# TI_MotorController.net
KiCad netlist of a schematic drawn in EAGLE
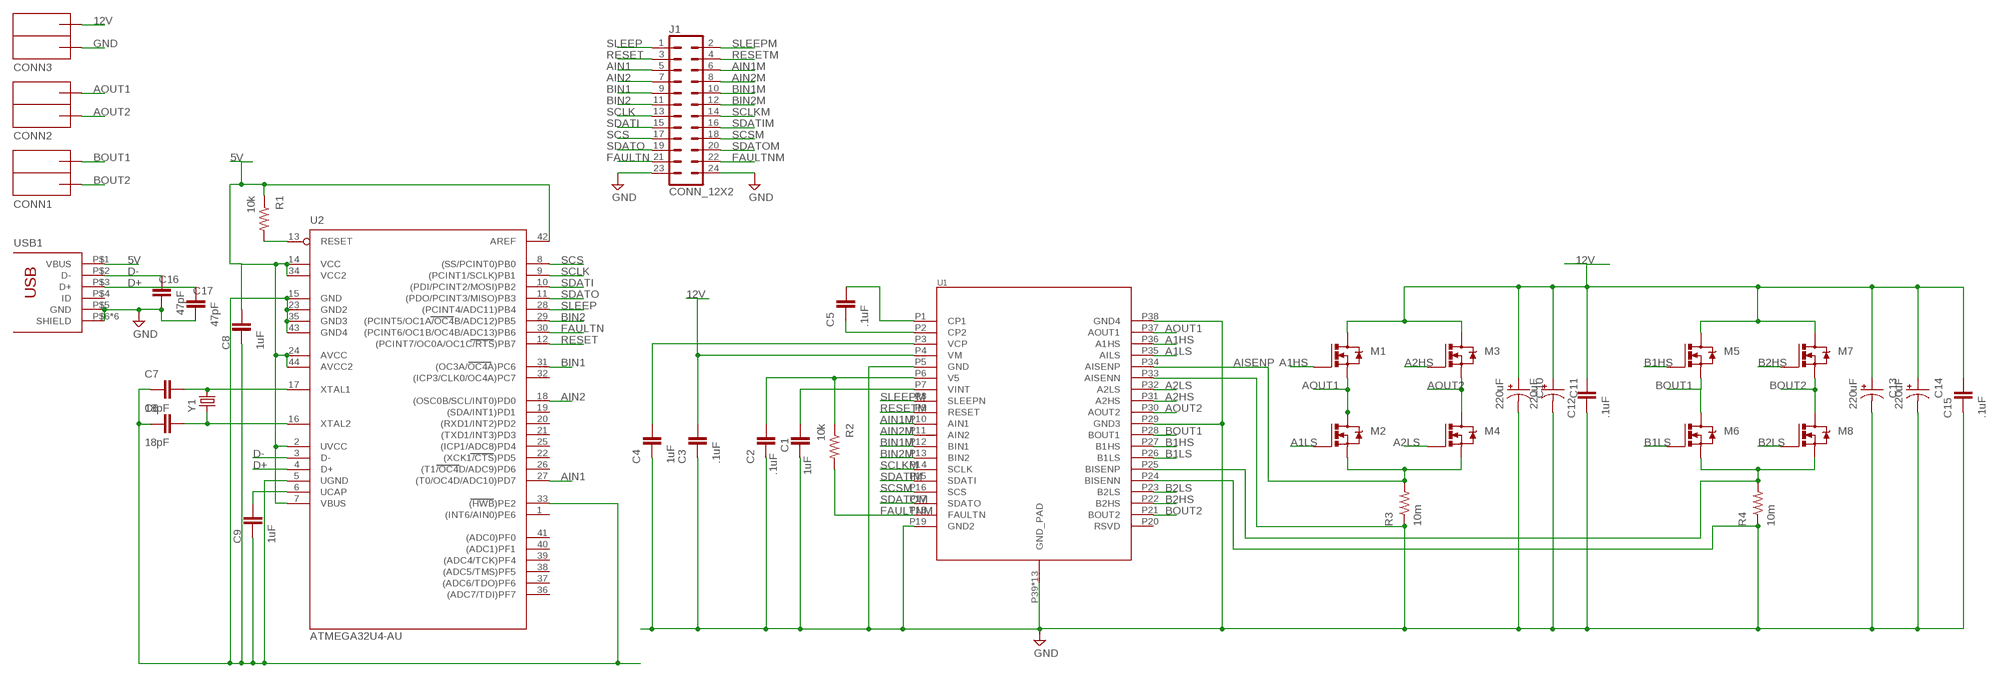
[diagram p0: schematic, sheet 1]

(export (version "E")
  (design (tool "Eeschema 10.0.6"))
  (components
    (comp (ref "C1")
      (value "1uF")
      (footprint "eagle-import:0603-CAP")
      (libsource (lib "eagle-import") (part "CAP0603-CAP"))
    )
    (comp (ref "C2")
      (value ".1uF")
      (footprint "eagle-import:0603-CAP")
      (libsource (lib "eagle-import") (part "CAP0603-CAP"))
    )
    (comp (ref "C3")
      (value ".1uF")
      (footprint "eagle-import:0603-CAP")
      (libsource (lib "eagle-import") (part "CAP0603-CAP"))
    )
    (comp (ref "C4")
      (value "1uF")
      (footprint "eagle-import:0603-CAP")
      (libsource (lib "eagle-import") (part "CAP0603-CAP"))
    )
    (comp (ref "C5")
      (value ".1uF")
      (footprint "eagle-import:0603-CAP")
      (libsource (lib "eagle-import") (part "CAP0603-CAP"))
    )
    (comp (ref "C6")
      (value "18pF")
      (footprint "eagle-import:0603-CAP")
      (libsource (lib "eagle-import") (part "CAP0603-CAP"))
    )
    (comp (ref "C7")
      (value "18pF")
      (footprint "eagle-import:0603-CAP")
      (libsource (lib "eagle-import") (part "CAP0603-CAP"))
    )
    (comp (ref "C8")
      (value "1uF")
      (footprint "eagle-import:0603-CAP")
      (libsource (lib "eagle-import") (part "CAP0603-CAP"))
    )
    (comp (ref "C9")
      (value "1uF")
      (footprint "eagle-import:0603-CAP")
      (libsource (lib "eagle-import") (part "CAP0603-CAP"))
    )
    (comp (ref "C10")
      (value "220uF")
      (footprint "eagle-import:NIPPON_F80")
      (libsource (lib "eagle-import") (part "CAP_POLF80"))
    )
    (comp (ref "C11")
      (value "220uF")
      (footprint "eagle-import:NIPPON_F80")
      (libsource (lib "eagle-import") (part "CAP_POLF80"))
    )
    (comp (ref "C12")
      (value ".1uF")
      (footprint "eagle-import:0603-CAP")
      (libsource (lib "eagle-import") (part "CAP0603-CAP"))
    )
    (comp (ref "C13")
      (value "220uF")
      (footprint "eagle-import:NIPPON_F80")
      (libsource (lib "eagle-import") (part "CAP_POLF80"))
    )
    (comp (ref "C14")
      (value "220uF")
      (footprint "eagle-import:NIPPON_F80")
      (libsource (lib "eagle-import") (part "CAP_POLF80"))
    )
    (comp (ref "C15")
      (value ".1uF")
      (footprint "eagle-import:0603-CAP")
      (libsource (lib "eagle-import") (part "CAP0603-CAP"))
    )
    (comp (ref "C16")
      (value "47pF")
      (footprint "eagle-import:0603-CAP")
      (libsource (lib "eagle-import") (part "CAP0603-CAP"))
    )
    (comp (ref "C17")
      (value "47pF")
      (footprint "eagle-import:0603-CAP")
      (libsource (lib "eagle-import") (part "CAP0603-CAP"))
    )
    (comp (ref "CONN1")
      (value "ANDERSONVERTICAL")
      (footprint "eagle-import:ANDERSON_VERTICAL")
      (libsource (lib "eagle-import") (part "ANDERSONVERTICAL"))
    )
    (comp (ref "CONN2")
      (value "ANDERSONVERTICAL")
      (footprint "eagle-import:ANDERSON_VERTICAL")
      (libsource (lib "eagle-import") (part "ANDERSONVERTICAL"))
    )
    (comp (ref "CONN3")
      (value "ANDERSONVERTICAL")
      (footprint "eagle-import:ANDERSON_VERTICAL")
      (libsource (lib "eagle-import") (part "ANDERSONVERTICAL"))
    )
    (comp (ref "J1")
      (value "CONN_12X2")
      (footprint "eagle-import:2X12")
      (libsource (lib "eagle-import") (part "CONN_12X2"))
    )
    (comp (ref "M1")
      (value "NMOS_CSD17579Q3A")
      (footprint "eagle-import:DNH0008A")
      (fields (field (name "PART_NO") "CSD17579Q3A"))
      (libsource (lib "eagle-import") (part "NMOS_CSD17579Q3A"))
    )
    (comp (ref "M2")
      (value "NMOS_CSD17579Q3A")
      (footprint "eagle-import:DNH0008A")
      (fields (field (name "PART_NO") "CSD17579Q3A"))
      (libsource (lib "eagle-import") (part "NMOS_CSD17579Q3A"))
    )
    (comp (ref "M3")
      (value "NMOS_CSD17579Q3A")
      (footprint "eagle-import:DNH0008A")
      (fields (field (name "PART_NO") "CSD17579Q3A"))
      (libsource (lib "eagle-import") (part "NMOS_CSD17579Q3A"))
    )
    (comp (ref "M4")
      (value "NMOS_CSD17579Q3A")
      (footprint "eagle-import:DNH0008A")
      (fields (field (name "PART_NO") "CSD17579Q3A"))
      (libsource (lib "eagle-import") (part "NMOS_CSD17579Q3A"))
    )
    (comp (ref "M5")
      (value "NMOS_CSD17579Q3A")
      (footprint "eagle-import:DNH0008A")
      (fields (field (name "PART_NO") "CSD17579Q3A"))
      (libsource (lib "eagle-import") (part "NMOS_CSD17579Q3A"))
    )
    (comp (ref "M6")
      (value "NMOS_CSD17579Q3A")
      (footprint "eagle-import:DNH0008A")
      (fields (field (name "PART_NO") "CSD17579Q3A"))
      (libsource (lib "eagle-import") (part "NMOS_CSD17579Q3A"))
    )
    (comp (ref "M7")
      (value "NMOS_CSD17579Q3A")
      (footprint "eagle-import:DNH0008A")
      (fields (field (name "PART_NO") "CSD17579Q3A"))
      (libsource (lib "eagle-import") (part "NMOS_CSD17579Q3A"))
    )
    (comp (ref "M8")
      (value "NMOS_CSD17579Q3A")
      (footprint "eagle-import:DNH0008A")
      (fields (field (name "PART_NO") "CSD17579Q3A"))
      (libsource (lib "eagle-import") (part "NMOS_CSD17579Q3A"))
    )
    (comp (ref "R1")
      (value "10k")
      (footprint "eagle-import:R0603")
      (fields (field (name "MANUFACTURER") "Rohm Semiconductor"))
      (libsource (lib "eagle-import") (part "R-US_R0603"))
    )
    (comp (ref "R2")
      (value "10k")
      (footprint "eagle-import:R0603")
      (fields (field (name "MANUFACTURER") "Rohm Semiconductor"))
      (libsource (lib "eagle-import") (part "R-US_R0603"))
    )
    (comp (ref "R3")
      (value "10m")
      (footprint "eagle-import:R2512")
      (libsource (lib "eagle-import") (part "R-US_R2512"))
    )
    (comp (ref "R4")
      (value "10m")
      (footprint "eagle-import:R2512")
      (libsource (lib "eagle-import") (part "R-US_R2512"))
    )
    (comp (ref "U1")
      (value "DRV8704")
      (footprint "eagle-import:HTSSOP(38)")
      (libsource (lib "eagle-import") (part "DRV8704"))
    )
    (comp (ref "U2")
      (value "ATMEGA32U4-AU")
      (footprint "eagle-import:TQFP44")
      (libsource (lib "eagle-import") (part "ATMEGA32U4-AU"))
    )
    (comp (ref "USB1")
      (value "USB-OTGMICRO-AB")
      (footprint "eagle-import:USB-MICRO-AB")
      (libsource (lib "eagle-import") (part "USB-OTGMICRO-AB"))
    )
    (comp (ref "Y1")
      (value "CRYSTAL10.5X4.8")
      (footprint "eagle-import:CRYSTAL-SMD-10.5X4.8-2PIN")
      (libsource (lib "eagle-import") (part "CRYSTAL10.5X4.8"))
    )
  )
  (nets
    (net (code "1") (name "/5V") (class "Default")
      (node (ref "C8") (pin "2") (pinfunction "2_2") (pintype "passive"))
      (node (ref "R1") (pin "1") (pinfunction "1_1") (pintype "passive"))
      (node (ref "U2") (pin "14") (pinfunction "VCC_14") (pintype "bidirectional"))
      (node (ref "U2") (pin "2") (pinfunction "UVCC_2") (pintype "bidirectional"))
      (node (ref "U2") (pin "24") (pinfunction "AVCC_24") (pintype "bidirectional"))
      (node (ref "U2") (pin "34") (pinfunction "VCC2_34") (pintype "bidirectional"))
      (node (ref "U2") (pin "42") (pinfunction "AREF_42") (pintype "bidirectional"))
      (node (ref "U2") (pin "44") (pinfunction "AVCC2_44") (pintype "bidirectional"))
      (node (ref "U2") (pin "7") (pinfunction "VBUS_7") (pintype "bidirectional"))
      (node (ref "USB1") (pin "P$1") (pinfunction "VBUS_P$1") (pintype "bidirectional"))
    )
    (net (code "2") (name "/12V") (class "Default")
      (node (ref "C10") (pin "+") (pinfunction "+_+") (pintype "passive"))
      (node (ref "C11") (pin "+") (pinfunction "+_+") (pintype "passive"))
      (node (ref "C12") (pin "2") (pinfunction "2_2") (pintype "passive"))
      (node (ref "C13") (pin "+") (pinfunction "+_+") (pintype "passive"))
      (node (ref "C14") (pin "+") (pinfunction "+_+") (pintype "passive"))
      (node (ref "C15") (pin "2") (pinfunction "2_2") (pintype "passive"))
      (node (ref "C3") (pin "2") (pinfunction "2_2") (pintype "passive"))
      (node (ref "CONN3") (pin "PIN1") (pinfunction "OUTB_PIN1") (pintype "bidirectional"))
      (node (ref "M1") (pin "5") (pinfunction "D_5") (pintype "passive"))
      (node (ref "M1") (pin "6") (pinfunction "D_6") (pintype "passive"))
      (node (ref "M1") (pin "7") (pinfunction "D_7") (pintype "passive"))
      (node (ref "M1") (pin "8") (pinfunction "D_8") (pintype "passive"))
      (node (ref "M1") (pin "9") (pinfunction "D_9") (pintype "passive"))
      (node (ref "M3") (pin "5") (pinfunction "D_5") (pintype "passive"))
      (node (ref "M3") (pin "6") (pinfunction "D_6") (pintype "passive"))
      (node (ref "M3") (pin "7") (pinfunction "D_7") (pintype "passive"))
      (node (ref "M3") (pin "8") (pinfunction "D_8") (pintype "passive"))
      (node (ref "M3") (pin "9") (pinfunction "D_9") (pintype "passive"))
      (node (ref "M5") (pin "5") (pinfunction "D_5") (pintype "passive"))
      (node (ref "M5") (pin "6") (pinfunction "D_6") (pintype "passive"))
      (node (ref "M5") (pin "7") (pinfunction "D_7") (pintype "passive"))
      (node (ref "M5") (pin "8") (pinfunction "D_8") (pintype "passive"))
      (node (ref "M5") (pin "9") (pinfunction "D_9") (pintype "passive"))
      (node (ref "M7") (pin "5") (pinfunction "D_5") (pintype "passive"))
      (node (ref "M7") (pin "6") (pinfunction "D_6") (pintype "passive"))
      (node (ref "M7") (pin "7") (pinfunction "D_7") (pintype "passive"))
      (node (ref "M7") (pin "8") (pinfunction "D_8") (pintype "passive"))
      (node (ref "M7") (pin "9") (pinfunction "D_9") (pintype "passive"))
      (node (ref "U1") (pin "P4") (pinfunction "VM_P4") (pintype "bidirectional"))
    )
    (net (code "3") (name "/A1HS") (class "Default")
      (node (ref "M1") (pin "4") (pinfunction "G_4") (pintype "passive"))
      (node (ref "U1") (pin "P36") (pinfunction "A1HS_P36") (pintype "bidirectional"))
    )
    (net (code "4") (name "/A1LS") (class "Default")
      (node (ref "M2") (pin "4") (pinfunction "G_4") (pintype "passive"))
      (node (ref "U1") (pin "P35") (pinfunction "AILS_P35") (pintype "bidirectional"))
    )
    (net (code "5") (name "/A2HS") (class "Default")
      (node (ref "M3") (pin "4") (pinfunction "G_4") (pintype "passive"))
      (node (ref "U1") (pin "P31") (pinfunction "A2HS_P31") (pintype "bidirectional"))
    )
    (net (code "6") (name "/A2LS") (class "Default")
      (node (ref "M4") (pin "4") (pinfunction "G_4") (pintype "passive"))
      (node (ref "U1") (pin "P32") (pinfunction "A2LS_P32") (pintype "bidirectional"))
    )
    (net (code "7") (name "/AIN1") (class "Default")
      (node (ref "J1") (pin "5") (pinfunction "5_5") (pintype "passive"))
      (node (ref "U2") (pin "27") (pinfunction "(T0/OC4D/ADC10)PD7_27") (pintype "bidirectional"))
    )
    (net (code "8") (name "/AIN1M") (class "Default")
      (node (ref "J1") (pin "6") (pinfunction "6_6") (pintype "passive"))
      (node (ref "U1") (pin "P10") (pinfunction "AIN1_P10") (pintype "bidirectional"))
    )
    (net (code "9") (name "/AIN2") (class "Default")
      (node (ref "J1") (pin "7") (pinfunction "7_7") (pintype "passive"))
      (node (ref "U2") (pin "18") (pinfunction "(OSC0B/SCL/INT0)PD0_18") (pintype "bidirectional"))
    )
    (net (code "10") (name "/AIN2M") (class "Default")
      (node (ref "J1") (pin "8") (pinfunction "8_8") (pintype "passive"))
      (node (ref "U1") (pin "P11") (pinfunction "AIN2_P11") (pintype "bidirectional"))
    )
    (net (code "11") (name "/AISENP") (class "Default")
      (node (ref "M2") (pin "1") (pinfunction "S_1") (pintype "passive"))
      (node (ref "M2") (pin "2") (pinfunction "S_2") (pintype "passive"))
      (node (ref "M2") (pin "3") (pinfunction "S_3") (pintype "passive"))
      (node (ref "M4") (pin "1") (pinfunction "S_1") (pintype "passive"))
      (node (ref "M4") (pin "2") (pinfunction "S_2") (pintype "passive"))
      (node (ref "M4") (pin "3") (pinfunction "S_3") (pintype "passive"))
      (node (ref "R3") (pin "2") (pinfunction "2_2") (pintype "passive"))
      (node (ref "U1") (pin "P34") (pinfunction "AISENP_P34") (pintype "bidirectional"))
    )
    (net (code "12") (name "/AOUT1") (class "Default")
      (node (ref "CONN2") (pin "PIN1") (pinfunction "OUTB_PIN1") (pintype "bidirectional"))
      (node (ref "M1") (pin "1") (pinfunction "S_1") (pintype "passive"))
      (node (ref "M1") (pin "2") (pinfunction "S_2") (pintype "passive"))
      (node (ref "M1") (pin "3") (pinfunction "S_3") (pintype "passive"))
      (node (ref "M2") (pin "5") (pinfunction "D_5") (pintype "passive"))
      (node (ref "M2") (pin "6") (pinfunction "D_6") (pintype "passive"))
      (node (ref "M2") (pin "7") (pinfunction "D_7") (pintype "passive"))
      (node (ref "M2") (pin "8") (pinfunction "D_8") (pintype "passive"))
      (node (ref "M2") (pin "9") (pinfunction "D_9") (pintype "passive"))
      (node (ref "U1") (pin "P37") (pinfunction "AOUT1_P37") (pintype "bidirectional"))
    )
    (net (code "13") (name "/AOUT2") (class "Default")
      (node (ref "CONN2") (pin "PIN2") (pinfunction "OUTA_PIN2") (pintype "bidirectional"))
      (node (ref "M3") (pin "1") (pinfunction "S_1") (pintype "passive"))
      (node (ref "M3") (pin "2") (pinfunction "S_2") (pintype "passive"))
      (node (ref "M3") (pin "3") (pinfunction "S_3") (pintype "passive"))
      (node (ref "M4") (pin "5") (pinfunction "D_5") (pintype "passive"))
      (node (ref "M4") (pin "6") (pinfunction "D_6") (pintype "passive"))
      (node (ref "M4") (pin "7") (pinfunction "D_7") (pintype "passive"))
      (node (ref "M4") (pin "8") (pinfunction "D_8") (pintype "passive"))
      (node (ref "M4") (pin "9") (pinfunction "D_9") (pintype "passive"))
      (node (ref "U1") (pin "P30") (pinfunction "AOUT2_P30") (pintype "bidirectional"))
    )
    (net (code "14") (name "/B1HS") (class "Default")
      (node (ref "M5") (pin "4") (pinfunction "G_4") (pintype "passive"))
      (node (ref "U1") (pin "P27") (pinfunction "B1HS_P27") (pintype "bidirectional"))
    )
    (net (code "15") (name "/B1LS") (class "Default")
      (node (ref "M6") (pin "4") (pinfunction "G_4") (pintype "passive"))
      (node (ref "U1") (pin "P26") (pinfunction "B1LS_P26") (pintype "bidirectional"))
    )
    (net (code "16") (name "/B2HS") (class "Default")
      (node (ref "M7") (pin "4") (pinfunction "G_4") (pintype "passive"))
      (node (ref "U1") (pin "P22") (pinfunction "B2HS_P22") (pintype "bidirectional"))
    )
    (net (code "17") (name "/B2LS") (class "Default")
      (node (ref "M8") (pin "4") (pinfunction "G_4") (pintype "passive"))
      (node (ref "U1") (pin "P23") (pinfunction "B2LS_P23") (pintype "bidirectional"))
    )
    (net (code "18") (name "/BIN1") (class "Default")
      (node (ref "J1") (pin "9") (pinfunction "9_9") (pintype "passive"))
      (node (ref "U2") (pin "31") (pinfunction "(OC3A/OC4A)PC6_31") (pintype "bidirectional"))
    )
    (net (code "19") (name "/BIN1M") (class "Default")
      (node (ref "J1") (pin "10") (pinfunction "10_10") (pintype "passive"))
      (node (ref "U1") (pin "P12") (pinfunction "BIN1_P12") (pintype "bidirectional"))
    )
    (net (code "20") (name "/BIN2") (class "Default")
      (node (ref "J1") (pin "11") (pinfunction "11_11") (pintype "passive"))
      (node (ref "U2") (pin "29") (pinfunction "(PCINT5/OC1A/OC4B/ADC12)PB5_29") (pintype "bidirectional"))
    )
    (net (code "21") (name "/BIN2M") (class "Default")
      (node (ref "J1") (pin "12") (pinfunction "12_12") (pintype "passive"))
      (node (ref "U1") (pin "P13") (pinfunction "BIN2_P13") (pintype "bidirectional"))
    )
    (net (code "22") (name "/BOUT1") (class "Default")
      (node (ref "CONN1") (pin "PIN1") (pinfunction "OUTB_PIN1") (pintype "bidirectional"))
      (node (ref "M5") (pin "1") (pinfunction "S_1") (pintype "passive"))
      (node (ref "M5") (pin "2") (pinfunction "S_2") (pintype "passive"))
      (node (ref "M5") (pin "3") (pinfunction "S_3") (pintype "passive"))
      (node (ref "M6") (pin "5") (pinfunction "D_5") (pintype "passive"))
      (node (ref "M6") (pin "6") (pinfunction "D_6") (pintype "passive"))
      (node (ref "M6") (pin "7") (pinfunction "D_7") (pintype "passive"))
      (node (ref "M6") (pin "8") (pinfunction "D_8") (pintype "passive"))
      (node (ref "M6") (pin "9") (pinfunction "D_9") (pintype "passive"))
      (node (ref "U1") (pin "P28") (pinfunction "BOUT1_P28") (pintype "bidirectional"))
    )
    (net (code "23") (name "/BOUT2") (class "Default")
      (node (ref "CONN1") (pin "PIN2") (pinfunction "OUTA_PIN2") (pintype "bidirectional"))
      (node (ref "M7") (pin "1") (pinfunction "S_1") (pintype "passive"))
      (node (ref "M7") (pin "2") (pinfunction "S_2") (pintype "passive"))
      (node (ref "M7") (pin "3") (pinfunction "S_3") (pintype "passive"))
      (node (ref "M8") (pin "5") (pinfunction "D_5") (pintype "passive"))
      (node (ref "M8") (pin "6") (pinfunction "D_6") (pintype "passive"))
      (node (ref "M8") (pin "7") (pinfunction "D_7") (pintype "passive"))
      (node (ref "M8") (pin "8") (pinfunction "D_8") (pintype "passive"))
      (node (ref "M8") (pin "9") (pinfunction "D_9") (pintype "passive"))
      (node (ref "U1") (pin "P21") (pinfunction "BOUT2_P21") (pintype "bidirectional"))
    )
    (net (code "24") (name "/D+") (class "Default")
      (node (ref "C17") (pin "2") (pinfunction "2_2") (pintype "passive"))
      (node (ref "U2") (pin "4") (pinfunction "D+_4") (pintype "bidirectional"))
      (node (ref "USB1") (pin "P$3") (pinfunction "D+_P$3") (pintype "bidirectional"))
    )
    (net (code "25") (name "/D-") (class "Default")
      (node (ref "C16") (pin "2") (pinfunction "2_2") (pintype "passive"))
      (node (ref "U2") (pin "3") (pinfunction "D-_3") (pintype "bidirectional"))
      (node (ref "USB1") (pin "P$2") (pinfunction "D-_P$2") (pintype "bidirectional"))
    )
    (net (code "26") (name "/FAULTN") (class "Default")
      (node (ref "J1") (pin "21") (pinfunction "21_21") (pintype "passive"))
      (node (ref "U2") (pin "30") (pinfunction "(PCINT6/OC1B/OC4B/ADC13)PB6_30") (pintype "bidirectional"))
    )
    (net (code "27") (name "/FAULTNM") (class "Default")
      (node (ref "J1") (pin "22") (pinfunction "22_22") (pintype "passive"))
      (node (ref "R2") (pin "2") (pinfunction "2_2") (pintype "passive"))
      (node (ref "U1") (pin "P18") (pinfunction "FAULTN_P18") (pintype "bidirectional"))
    )
    (net (code "28") (name "/RESET") (class "Default")
      (node (ref "J1") (pin "3") (pinfunction "3_3") (pintype "passive"))
      (node (ref "U2") (pin "12") (pinfunction "(PCINT7/OC0A/OC1C/RTS)PB7_12") (pintype "bidirectional"))
    )
    (net (code "29") (name "/RESETM") (class "Default")
      (node (ref "J1") (pin "4") (pinfunction "4_4") (pintype "passive"))
      (node (ref "U1") (pin "P9") (pinfunction "RESET_P9") (pintype "bidirectional"))
    )
    (net (code "30") (name "/SCLK") (class "Default")
      (node (ref "J1") (pin "13") (pinfunction "13_13") (pintype "passive"))
      (node (ref "U2") (pin "9") (pinfunction "(PCINT1/SCLK)PB1_9") (pintype "bidirectional"))
    )
    (net (code "31") (name "/SCLKM") (class "Default")
      (node (ref "J1") (pin "14") (pinfunction "14_14") (pintype "passive"))
      (node (ref "U1") (pin "P14") (pinfunction "SCLK_P14") (pintype "bidirectional"))
    )
    (net (code "32") (name "/SCS") (class "Default")
      (node (ref "J1") (pin "17") (pinfunction "17_17") (pintype "passive"))
      (node (ref "U2") (pin "8") (pinfunction "(SS/PCINT0)PB0_8") (pintype "bidirectional"))
    )
    (net (code "33") (name "/SCSM") (class "Default")
      (node (ref "J1") (pin "18") (pinfunction "18_18") (pintype "passive"))
      (node (ref "U1") (pin "P16") (pinfunction "SCS_P16") (pintype "bidirectional"))
    )
    (net (code "34") (name "/SDATI") (class "Default")
      (node (ref "J1") (pin "15") (pinfunction "15_15") (pintype "passive"))
      (node (ref "U2") (pin "10") (pinfunction "(PDI/PCINT2/MOSI)PB2_10") (pintype "bidirectional"))
    )
    (net (code "35") (name "/SDATIM") (class "Default")
      (node (ref "J1") (pin "16") (pinfunction "16_16") (pintype "passive"))
      (node (ref "U1") (pin "P15") (pinfunction "SDATI_P15") (pintype "bidirectional"))
    )
    (net (code "36") (name "/SDATO") (class "Default")
      (node (ref "J1") (pin "19") (pinfunction "19_19") (pintype "passive"))
      (node (ref "U2") (pin "11") (pinfunction "(PDO/PCINT3/MISO)PB3_11") (pintype "bidirectional"))
    )
    (net (code "37") (name "/SDATOM") (class "Default")
      (node (ref "J1") (pin "20") (pinfunction "20_20") (pintype "passive"))
      (node (ref "U1") (pin "P17") (pinfunction "SDATO_P17") (pintype "bidirectional"))
    )
    (net (code "38") (name "/SLEEP") (class "Default")
      (node (ref "J1") (pin "1") (pinfunction "1_1") (pintype "passive"))
      (node (ref "U2") (pin "28") (pinfunction "(PCINT4/ADC11)PB4_28") (pintype "bidirectional"))
    )
    (net (code "39") (name "/SLEEPM") (class "Default")
      (node (ref "J1") (pin "2") (pinfunction "2_2") (pintype "passive"))
      (node (ref "U1") (pin "P8") (pinfunction "SLEEPN_P8") (pintype "bidirectional"))
    )
    (net (code "40") (name "GND") (class "Default")
      (node (ref "C1") (pin "1") (pinfunction "1_1") (pintype "passive"))
      (node (ref "C10") (pin "-") (pinfunction "-_-") (pintype "passive"))
      (node (ref "C11") (pin "-") (pinfunction "-_-") (pintype "passive"))
      (node (ref "C12") (pin "1") (pinfunction "1_1") (pintype "passive"))
      (node (ref "C13") (pin "-") (pinfunction "-_-") (pintype "passive"))
      (node (ref "C14") (pin "-") (pinfunction "-_-") (pintype "passive"))
      (node (ref "C15") (pin "1") (pinfunction "1_1") (pintype "passive"))
      (node (ref "C16") (pin "1") (pinfunction "1_1") (pintype "passive"))
      (node (ref "C17") (pin "1") (pinfunction "1_1") (pintype "passive"))
      (node (ref "C2") (pin "1") (pinfunction "1_1") (pintype "passive"))
      (node (ref "C3") (pin "1") (pinfunction "1_1") (pintype "passive"))
      (node (ref "C4") (pin "1") (pinfunction "1_1") (pintype "passive"))
      (node (ref "CONN3") (pin "PIN2") (pinfunction "OUTA_PIN2") (pintype "bidirectional"))
      (node (ref "J1") (pin "23") (pinfunction "23_23") (pintype "passive"))
      (node (ref "J1") (pin "24") (pinfunction "24_24") (pintype "passive"))
      (node (ref "R3") (pin "1") (pinfunction "1_1") (pintype "passive"))
      (node (ref "R4") (pin "1") (pinfunction "1_1") (pintype "passive"))
      (node (ref "U1") (pin "P19") (pinfunction "GND2_P19") (pintype "bidirectional"))
      (node (ref "U1") (pin "P24") (pinfunction "BISENN_P24") (pintype "bidirectional"))
      (node (ref "U1") (pin "P29") (pinfunction "GND3_P29") (pintype "bidirectional"))
      (node (ref "U1") (pin "P33") (pinfunction "AISENN_P33") (pintype "bidirectional"))
      (node (ref "U1") (pin "P38") (pinfunction "GND4_P38") (pintype "bidirectional"))
      (node (ref "U1") (pin "P39") (pinfunction "GND_PAD_P39") (pintype "bidirectional"))
      (node (ref "U1") (pin "P40") (pinfunction "GND_PAD_P40") (pintype "bidirectional"))
      (node (ref "U1") (pin "P41") (pinfunction "GND_PAD_P41") (pintype "bidirectional"))
      (node (ref "U1") (pin "P42") (pinfunction "GND_PAD_P42") (pintype "bidirectional"))
      (node (ref "U1") (pin "P43") (pinfunction "GND_PAD_P43") (pintype "bidirectional"))
      (node (ref "U1") (pin "P44") (pinfunction "GND_PAD_P44") (pintype "bidirectional"))
      (node (ref "U1") (pin "P45") (pinfunction "GND_PAD_P45") (pintype "bidirectional"))
      (node (ref "U1") (pin "P46") (pinfunction "GND_PAD_P46") (pintype "bidirectional"))
      (node (ref "U1") (pin "P47") (pinfunction "GND_PAD_P47") (pintype "bidirectional"))
      (node (ref "U1") (pin "P48") (pinfunction "GND_PAD_P48") (pintype "bidirectional"))
      (node (ref "U1") (pin "P49") (pinfunction "GND_PAD_P49") (pintype "bidirectional"))
      (node (ref "U1") (pin "P5") (pinfunction "GND_P5") (pintype "bidirectional"))
      (node (ref "U1") (pin "P50") (pinfunction "GND_PAD_P50") (pintype "bidirectional"))
      (node (ref "U1") (pin "P51") (pinfunction "GND_PAD_P51") (pintype "bidirectional"))
      (node (ref "USB1") (pin "P$10") (pinfunction "SHIELD_P$10") (pintype "bidirectional"))
      (node (ref "USB1") (pin "P$11") (pinfunction "SHIELD_P$11") (pintype "bidirectional"))
      (node (ref "USB1") (pin "P$5") (pinfunction "GND_P$5") (pintype "bidirectional"))
      (node (ref "USB1") (pin "P$6") (pinfunction "SHIELD_P$6") (pintype "bidirectional"))
      (node (ref "USB1") (pin "P$7") (pinfunction "SHIELD_P$7") (pintype "bidirectional"))
      (node (ref "USB1") (pin "P$8") (pinfunction "SHIELD_P$8") (pintype "bidirectional"))
      (node (ref "USB1") (pin "P$9") (pinfunction "SHIELD_P$9") (pintype "bidirectional"))
    )
    (net (code "41") (name "Net-(U1-BISENP)") (class "Default")
      (node (ref "M6") (pin "1") (pinfunction "S_1") (pintype "passive"))
      (node (ref "M6") (pin "2") (pinfunction "S_2") (pintype "passive"))
      (node (ref "M6") (pin "3") (pinfunction "S_3") (pintype "passive"))
      (node (ref "M8") (pin "1") (pinfunction "S_1") (pintype "passive"))
      (node (ref "M8") (pin "2") (pinfunction "S_2") (pintype "passive"))
      (node (ref "M8") (pin "3") (pinfunction "S_3") (pintype "passive"))
      (node (ref "R4") (pin "2") (pinfunction "2_2") (pintype "passive"))
      (node (ref "U1") (pin "P25") (pinfunction "BISENP_P25") (pintype "bidirectional"))
    )
    (net (code "42") (name "Net-(U1-CP1)") (class "Default")
      (node (ref "C5") (pin "2") (pinfunction "2_2") (pintype "passive"))
      (node (ref "U1") (pin "P1") (pinfunction "CP1_P1") (pintype "bidirectional"))
    )
    (net (code "43") (name "Net-(U1-CP2)") (class "Default")
      (node (ref "C5") (pin "1") (pinfunction "1_1") (pintype "passive"))
      (node (ref "U1") (pin "P2") (pinfunction "CP2_P2") (pintype "bidirectional"))
    )
    (net (code "44") (name "Net-(U1-V5)") (class "Default")
      (node (ref "C2") (pin "2") (pinfunction "2_2") (pintype "passive"))
      (node (ref "R2") (pin "1") (pinfunction "1_1") (pintype "passive"))
      (node (ref "U1") (pin "P6") (pinfunction "V5_P6") (pintype "bidirectional"))
    )
    (net (code "45") (name "Net-(U1-VCP)") (class "Default")
      (node (ref "C4") (pin "2") (pinfunction "2_2") (pintype "passive"))
      (node (ref "U1") (pin "P3") (pinfunction "VCP_P3") (pintype "bidirectional"))
    )
    (net (code "46") (name "Net-(U1-VINT)") (class "Default")
      (node (ref "C1") (pin "2") (pinfunction "2_2") (pintype "passive"))
      (node (ref "U1") (pin "P7") (pinfunction "VINT_P7") (pintype "bidirectional"))
    )
    (net (code "47") (name "Net-(U2-(HWB)PE2)") (class "Default")
      (node (ref "C6") (pin "1") (pinfunction "1_1") (pintype "passive"))
      (node (ref "C7") (pin "1") (pinfunction "1_1") (pintype "passive"))
      (node (ref "C8") (pin "1") (pinfunction "1_1") (pintype "passive"))
      (node (ref "C9") (pin "1") (pinfunction "1_1") (pintype "passive"))
      (node (ref "U2") (pin "15") (pinfunction "GND_15") (pintype "bidirectional"))
      (node (ref "U2") (pin "23") (pinfunction "GND2_23") (pintype "bidirectional"))
      (node (ref "U2") (pin "33") (pinfunction "(HWB)PE2_33") (pintype "bidirectional"))
      (node (ref "U2") (pin "35") (pinfunction "GND3_35") (pintype "bidirectional"))
      (node (ref "U2") (pin "43") (pinfunction "GND4_43") (pintype "bidirectional"))
      (node (ref "U2") (pin "5") (pinfunction "UGND_5") (pintype "bidirectional"))
    )
    (net (code "48") (name "Net-(U2-RESET)") (class "Default")
      (node (ref "R1") (pin "2") (pinfunction "2_2") (pintype "passive"))
      (node (ref "U2") (pin "13") (pinfunction "RESET_13") (pintype "bidirectional"))
    )
    (net (code "49") (name "Net-(U2-UCAP)") (class "Default")
      (node (ref "C9") (pin "2") (pinfunction "2_2") (pintype "passive"))
      (node (ref "U2") (pin "6") (pinfunction "UCAP_6") (pintype "bidirectional"))
    )
    (net (code "50") (name "Net-(U2-XTAL1)") (class "Default")
      (node (ref "C7") (pin "2") (pinfunction "2_2") (pintype "passive"))
      (node (ref "U2") (pin "17") (pinfunction "XTAL1_17") (pintype "bidirectional"))
      (node (ref "Y1") (pin "P$2") (pinfunction "2_P$2") (pintype "passive"))
    )
    (net (code "51") (name "Net-(U2-XTAL2)") (class "Default")
      (node (ref "C6") (pin "2") (pinfunction "2_2") (pintype "passive"))
      (node (ref "U2") (pin "16") (pinfunction "XTAL2_16") (pintype "bidirectional"))
      (node (ref "Y1") (pin "P$1") (pinfunction "1_P$1") (pintype "passive"))
    )
    (net (code "52") (name "unconnected-(U1-RSVD-PadP20)") (class "Default")
      (node (ref "U1") (pin "P20") (pinfunction "RSVD_P20") (pintype "bidirectional"))
    )
    (net (code "53") (name "unconnected-(U2-(ADC0)PF0-Pad41)") (class "Default")
      (node (ref "U2") (pin "41") (pinfunction "(ADC0)PF0_41") (pintype "bidirectional"))
    )
    (net (code "54") (name "unconnected-(U2-(ADC1)PF1-Pad40)") (class "Default")
      (node (ref "U2") (pin "40") (pinfunction "(ADC1)PF1_40") (pintype "bidirectional"))
    )
    (net (code "55") (name "unconnected-(U2-(ADC4{slash}TCK)PF4-Pad39)") (class "Default")
      (node (ref "U2") (pin "39") (pinfunction "(ADC4/TCK)PF4_39") (pintype "bidirectional"))
    )
    (net (code "56") (name "unconnected-(U2-(ADC5{slash}TMS)PF5-Pad38)") (class "Default")
      (node (ref "U2") (pin "38") (pinfunction "(ADC5/TMS)PF5_38") (pintype "bidirectional"))
    )
    (net (code "57") (name "unconnected-(U2-(ADC6{slash}TDO)PF6-Pad37)") (class "Default")
      (node (ref "U2") (pin "37") (pinfunction "(ADC6/TDO)PF6_37") (pintype "bidirectional"))
    )
    (net (code "58") (name "unconnected-(U2-(ADC7{slash}TDI)PF7-Pad36)") (class "Default")
      (node (ref "U2") (pin "36") (pinfunction "(ADC7/TDI)PF7_36") (pintype "bidirectional"))
    )
    (net (code "59") (name "unconnected-(U2-(ICP1{slash}ADC8)PD4-Pad25)") (class "Default")
      (node (ref "U2") (pin "25") (pinfunction "(ICP1/ADC8)PD4_25") (pintype "bidirectional"))
    )
    (net (code "60") (name "unconnected-(U2-(ICP3{slash}CLK0{slash}OC4A)PC7-Pad32)") (class "Default")
      (node (ref "U2") (pin "32") (pinfunction "(ICP3/CLK0/OC4A)PC7_32") (pintype "bidirectional"))
    )
    (net (code "61") (name "unconnected-(U2-(INT6{slash}AIN0)PE6-Pad1)") (class "Default")
      (node (ref "U2") (pin "1") (pinfunction "(INT6/AIN0)PE6_1") (pintype "bidirectional"))
    )
    (net (code "62") (name "unconnected-(U2-(RXD1{slash}INT2)PD2-Pad20)") (class "Default")
      (node (ref "U2") (pin "20") (pinfunction "(RXD1/INT2)PD2_20") (pintype "bidirectional"))
    )
    (net (code "63") (name "unconnected-(U2-(SDA{slash}INT1)PD1-Pad19)") (class "Default")
      (node (ref "U2") (pin "19") (pinfunction "(SDA/INT1)PD1_19") (pintype "bidirectional"))
    )
    (net (code "64") (name "unconnected-(U2-(T1{slash}OC4D{slash}ADC9)PD6-Pad26)") (class "Default")
      (node (ref "U2") (pin "26") (pinfunction "(T1/OC4D/ADC9)PD6_26") (pintype "bidirectional"))
    )
    (net (code "65") (name "unconnected-(U2-(TXD1{slash}INT3)PD3-Pad21)") (class "Default")
      (node (ref "U2") (pin "21") (pinfunction "(TXD1/INT3)PD3_21") (pintype "bidirectional"))
    )
    (net (code "66") (name "unconnected-(U2-(XCK1{slash}CTS)PD5-Pad22)") (class "Default")
      (node (ref "U2") (pin "22") (pinfunction "(XCK1/CTS)PD5_22") (pintype "bidirectional"))
    )
    (net (code "67") (name "unconnected-(USB1-ID-PadP$4)") (class "Default")
      (node (ref "USB1") (pin "P$4") (pinfunction "ID_P$4") (pintype "bidirectional"))
    )
  )
)
